# Sheet2-power.net
KiCad netlist of a schematic drawn in Altium Designer
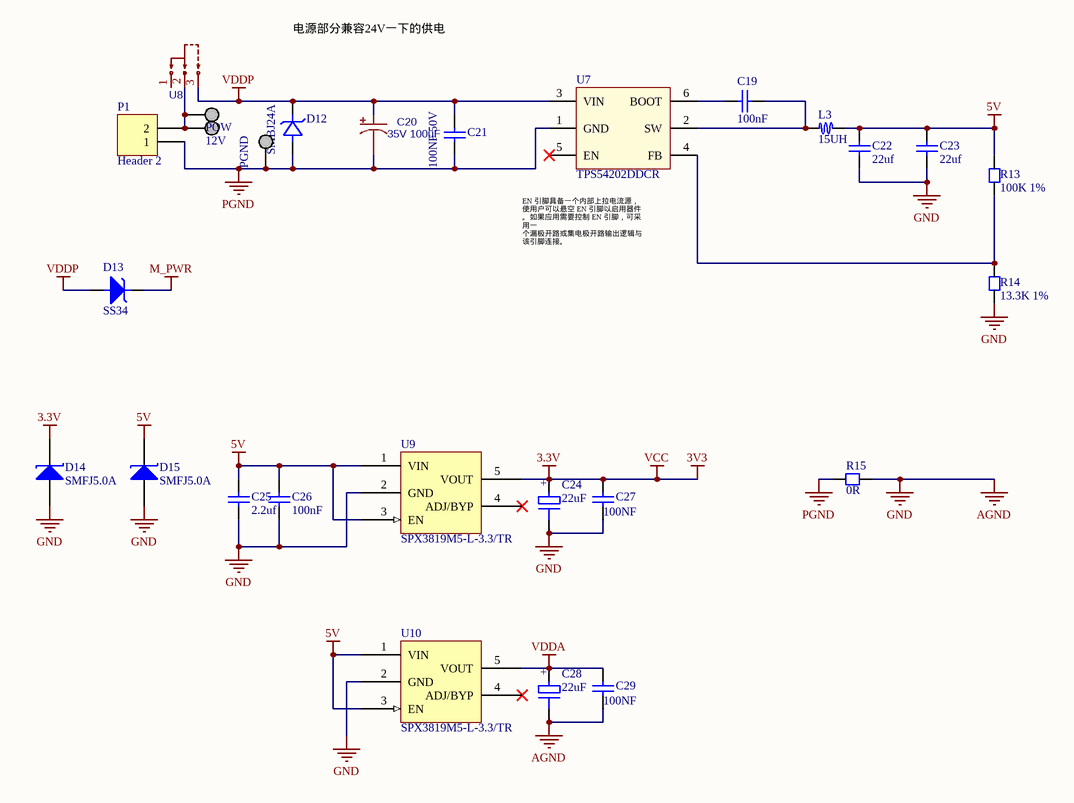
[diagram p0: Sheet2-power.SchDoc]

(export (version "E")
  (design (tool "Eeschema 10.0.6"))
  (components
    (comp (ref "12V")
      (value "test")
      (footprint "test")
      (description "测试点")
      (libsource (lib "base") (part "test"))
    )
    (comp (ref "C19")
      (value "100nF")
      (footprint "CC1608-0603")
      (description "0603封装的电容")
      (fields (field (name "PUBLISHER") "Altium Limited"))
      (libsource (lib "base") (part "Cap Chip 0603"))
    )
    (comp (ref "C20")
      (value "35V 100uF")
      (footprint "CAP-SMD_D6.3")
      (description "铝点解电容")
      (fields
        (field (name "BOM_SUPPLIER PART") "C413527")
        (field (name "BOM_MANUFACTURER PART") "EEEFP1C681AP")
        (field (name "CONTRIBUTOR") "LCSC")
      )
      (libsource (lib "base") (part "Cap ECAP SMD"))
    )
    (comp (ref "C21")
      (value "100NF 50V")
      (footprint "CC1608-0603")
      (description "0603封装的电容")
      (fields (field (name "PUBLISHER") "Altium Limited"))
      (libsource (lib "base") (part "Cap Chip 0603"))
    )
    (comp (ref "C22")
      (value "22uf")
      (footprint "CC1608-0603")
      (description "0603封装的电容")
      (fields (field (name "PUBLISHER") "Altium Limited"))
      (libsource (lib "base") (part "Cap Chip 0603"))
    )
    (comp (ref "C23")
      (value "22uf")
      (footprint "CC1608-0603")
      (description "0603封装的电容")
      (fields (field (name "PUBLISHER") "Altium Limited"))
      (libsource (lib "base") (part "Cap Chip 0603"))
    )
    (comp (ref "C24")
      (value "22uF")
      (footprint "TAN-A-1206")
      (description "钽电容")
      (libsource (lib "base") (part "CAP TAN-A-1206"))
    )
    (comp (ref "C25")
      (value "2.2uf")
      (footprint "CC1608-0603")
      (description "0603封装的电容")
      (fields (field (name "PUBLISHER") "Altium Limited"))
      (libsource (lib "base") (part "Cap Chip 0603"))
    )
    (comp (ref "C26")
      (value "100nF")
      (footprint "CC1608-0603")
      (description "0603封装的电容")
      (fields (field (name "PUBLISHER") "Altium Limited"))
      (libsource (lib "base") (part "Cap Chip 0603"))
    )
    (comp (ref "C27")
      (value "100NF")
      (footprint "CC1608-0603")
      (description "贴片电容")
      (libsource (lib "tianxiaohua_Schlib") (part "Chip capacitor"))
    )
    (comp (ref "C28")
      (value "22uF")
      (footprint "TAN-A-1206")
      (description "钽电容")
      (libsource (lib "base") (part "CAP TAN-A-1206"))
    )
    (comp (ref "C29")
      (value "100NF")
      (footprint "CC1608-0603")
      (description "贴片电容")
      (libsource (lib "tianxiaohua_Schlib") (part "Chip capacitor"))
    )
    (comp (ref "D12")
      (value "SMBJ24A")
      (footprint "DO-214 AA")
      (description "TVS稳压二极管")
      (libsource (lib "transistor") (part "SMBJ18A"))
    )
    (comp (ref "D13")
      (value "SS34")
      (footprint "DO-214 AA")
      (description "肖特基二极管")
      (libsource (lib "transistor") (part "SS34"))
    )
    (comp (ref "D14")
      (value "SMFJ5.0A")
      (footprint "SOD-123")
      (description "5V单向贴片TVS瞬变抑制二极管")
      (libsource (lib "transistor") (part "SMFJ5.0A"))
    )
    (comp (ref "D15")
      (value "SMFJ5.0A")
      (footprint "SOD-123")
      (description "5V单向贴片TVS瞬变抑制二极管")
      (libsource (lib "transistor") (part "SMFJ5.0A"))
    )
    (comp (ref "L3")
      (value "15UH")
      (footprint "Inductor-0630")
      (description "贴片电感 0630封装")
      (libsource (lib "base") (part "Inductor-0630"))
    )
    (comp (ref "P1")
      (value "Header 2")
      (footprint "HX2.54-2")
      (description "Header, 2-Pin")
      (fields (field (name "PUBLISHER") "Altium Limited"))
      (libsource (lib "Connectors") (part "Header 2"))
    )
    (comp (ref "PGND")
      (value "test")
      (footprint "test")
      (description "测试点")
      (libsource (lib "base") (part "test"))
    )
    (comp (ref "POW")
      (value "test")
      (footprint "test")
      (description "测试点")
      (libsource (lib "base") (part "test"))
    )
    (comp (ref "R13")
      (value "100K 1%")
      (footprint "CR1608-0603")
      (description "0603封装电阻")
      (fields (field (name "PUBLISHER") "Altium Limited"))
      (libsource (lib "base") (part "Resistor Chip 0603"))
    )
    (comp (ref "R14")
      (value "13.3K 1%")
      (footprint "CR1608-0603")
      (description "0603封装电阻")
      (fields (field (name "PUBLISHER") "Altium Limited"))
      (libsource (lib "base") (part "Resistor Chip 0603"))
    )
    (comp (ref "R15")
      (value "0R")
      (footprint "CR1608-0603")
      (description "0603封装电阻")
      (fields (field (name "PUBLISHER") "Altium Limited"))
      (libsource (lib "") (part "Resistor Chip 0603_1"))
    )
    (comp (ref "U7")
      (value "TPS54202DDCR")
      (footprint "SOT23-6")
      (description "同步降压转换器芯片 500Khz 4.2~28V输入，2A输出")
      (libsource (lib "power-chip") (part "TPS54202DDCR"))
    )
    (comp (ref "U8")
      (value "HX SS12D10G4")
      (footprint "SW-TH_3P-SS12D06")
      (fields (field (name "BOM_SUPPLIER PART") "C5149841") (field (name "CONTRIBUTOR") "lcsc"))
      (libsource (lib "base") (part "SW-TH_3P-SS12D06"))
    )
    (comp (ref "U9")
      (value "SPX3819M5-L-3.3/TR")
      (footprint "SOT23-5")
      (description "LDO 3.3V , SOT-23-5 500ma")
      (libsource (lib "power-chip") (part "SPX3819M5-L-3.3/TR"))
    )
    (comp (ref "U10")
      (value "SPX3819M5-L-3.3/TR")
      (footprint "SOT23-5")
      (description "LDO 3.3V , SOT-23-5 500ma")
      (libsource (lib "power-chip") (part "SPX3819M5-L-3.3/TR"))
    )
  )
  (nets
    (net (code "1") (name "3.3V") (class "Default")
      (node (ref "C24") (pin "1") (pinfunction "+_1") (pintype "passive"))
      (node (ref "C27") (pin "1") (pinfunction "1_1") (pintype "passive"))
      (node (ref "D14") (pin "1") (pinfunction "1_1") (pintype "passive"))
      (node (ref "U9") (pin "5") (pinfunction "VOUT_5") (pintype "passive"))
    )
    (net (code "2") (name "5V") (class "Default")
      (node (ref "C22") (pin "2") (pinfunction "2_2") (pintype "passive"))
      (node (ref "C23") (pin "2") (pinfunction "2_2") (pintype "passive"))
      (node (ref "C25") (pin "2") (pinfunction "2_2") (pintype "passive"))
      (node (ref "C26") (pin "2") (pinfunction "2_2") (pintype "passive"))
      (node (ref "D15") (pin "1") (pinfunction "1_1") (pintype "passive"))
      (node (ref "L3") (pin "2") (pinfunction "2_2") (pintype "passive"))
      (node (ref "R13") (pin "2") (pinfunction "2_2") (pintype "passive"))
      (node (ref "U10") (pin "1") (pinfunction "VIN_1") (pintype "power_in"))
      (node (ref "U10") (pin "3") (pinfunction "EN_3") (pintype "input"))
      (node (ref "U9") (pin "1") (pinfunction "VIN_1") (pintype "power_in"))
      (node (ref "U9") (pin "3") (pinfunction "EN_3") (pintype "input"))
    )
    (net (code "3") (name "AGND") (class "Default")
      (node (ref "C22") (pin "1") (pinfunction "1_1") (pintype "passive"))
      (node (ref "C23") (pin "1") (pinfunction "1_1") (pintype "passive"))
      (node (ref "C24") (pin "2") (pinfunction "-_2") (pintype "passive"))
      (node (ref "C25") (pin "1") (pinfunction "1_1") (pintype "passive"))
      (node (ref "C26") (pin "1") (pinfunction "1_1") (pintype "passive"))
      (node (ref "C27") (pin "2") (pinfunction "2_2") (pintype "passive"))
      (node (ref "C28") (pin "2") (pinfunction "-_2") (pintype "passive"))
      (node (ref "C29") (pin "2") (pinfunction "2_2") (pintype "passive"))
      (node (ref "D14") (pin "2") (pinfunction "2_2") (pintype "passive"))
      (node (ref "D15") (pin "2") (pinfunction "2_2") (pintype "passive"))
      (node (ref "R14") (pin "1") (pinfunction "1_1") (pintype "passive"))
      (node (ref "R15") (pin "1") (pinfunction "1_1") (pintype "passive"))
      (node (ref "U10") (pin "2") (pinfunction "GND_2") (pintype "power_in"))
      (node (ref "U9") (pin "2") (pinfunction "GND_2") (pintype "power_in"))
    )
    (net (code "4") (name "M_PWR") (class "Default")
      (node (ref "D13") (pin "1") (pinfunction "K_1") (pintype "passive"))
    )
    (net (code "5") (name "Net-(12V-Pad0)") (class "Default")
      (node (ref "12V") (pin "0") (pinfunction "0_0") (pintype "passive"))
      (node (ref "P1") (pin "2") (pinfunction "2_2") (pintype "passive"))
      (node (ref "POW") (pin "0") (pinfunction "0_0") (pintype "passive"))
      (node (ref "U8") (pin "2") (pinfunction "2_2") (pintype "passive"))
    )
    (net (code "6") (name "Net-(U7-BOOT)") (class "Default")
      (node (ref "C19") (pin "1") (pinfunction "1_1") (pintype "passive"))
      (node (ref "U7") (pin "6") (pinfunction "BOOT_6") (pintype "passive"))
    )
    (net (code "7") (name "Net-(U7-FB)") (class "Default")
      (node (ref "R13") (pin "1") (pinfunction "1_1") (pintype "passive"))
      (node (ref "R14") (pin "2") (pinfunction "2_2") (pintype "passive"))
      (node (ref "U7") (pin "4") (pinfunction "FB_4") (pintype "passive"))
    )
    (net (code "8") (name "Net-(U7-SW)") (class "Default")
      (node (ref "C19") (pin "2") (pinfunction "2_2") (pintype "passive"))
      (node (ref "L3") (pin "1") (pinfunction "1_1") (pintype "passive"))
      (node (ref "U7") (pin "2") (pinfunction "SW_2") (pintype "passive"))
    )
    (net (code "9") (name "PGND") (class "Default")
      (node (ref "C20") (pin "2") (pinfunction "2_2") (pintype "passive"))
      (node (ref "C21") (pin "1") (pinfunction "1_1") (pintype "passive"))
      (node (ref "D12") (pin "2") (pinfunction "A_2") (pintype "passive"))
      (node (ref "P1") (pin "1") (pinfunction "1_1") (pintype "passive"))
      (node (ref "PGND") (pin "0") (pinfunction "0_0") (pintype "passive"))
      (node (ref "R15") (pin "2") (pinfunction "2_2") (pintype "passive"))
      (node (ref "U7") (pin "1") (pinfunction "GND_1") (pintype "passive"))
    )
    (net (code "10") (name "VDDA") (class "Default")
      (node (ref "C28") (pin "1") (pinfunction "+_1") (pintype "passive"))
      (node (ref "C29") (pin "1") (pinfunction "1_1") (pintype "passive"))
      (node (ref "U10") (pin "5") (pinfunction "VOUT_5") (pintype "passive"))
    )
    (net (code "11") (name "VDDP") (class "Default")
      (node (ref "C20") (pin "1") (pinfunction "1_1") (pintype "passive"))
      (node (ref "C21") (pin "2") (pinfunction "2_2") (pintype "passive"))
      (node (ref "D12") (pin "1") (pinfunction "K_1") (pintype "passive"))
      (node (ref "D13") (pin "2") (pinfunction "A_2") (pintype "passive"))
      (node (ref "U7") (pin "3") (pinfunction "VIN_3") (pintype "passive"))
      (node (ref "U8") (pin "3") (pinfunction "3_3") (pintype "passive"))
    )
    (net (code "12") (name "unconnected-(U7-EN-Pad5)") (class "Default")
      (node (ref "U7") (pin "5") (pinfunction "EN_5") (pintype "passive+no_connect"))
    )
    (net (code "13") (name "unconnected-(U8-Pad1)") (class "Default")
      (node (ref "U8") (pin "1") (pinfunction "1_1") (pintype "passive"))
    )
    (net (code "14") (name "unconnected-(U9-ADJ{slash}BYP-Pad4)") (class "Default")
      (node (ref "U9") (pin "4") (pinfunction "ADJ/BYP_4") (pintype "passive+no_connect"))
    )
    (net (code "15") (name "unconnected-(U10-ADJ{slash}BYP-Pad4)") (class "Default")
      (node (ref "U10") (pin "4") (pinfunction "ADJ/BYP_4") (pintype "passive+no_connect"))
    )
  )
)
